# TC4nano_v2.net
KiCad netlist of a schematic drawn in EAGLE
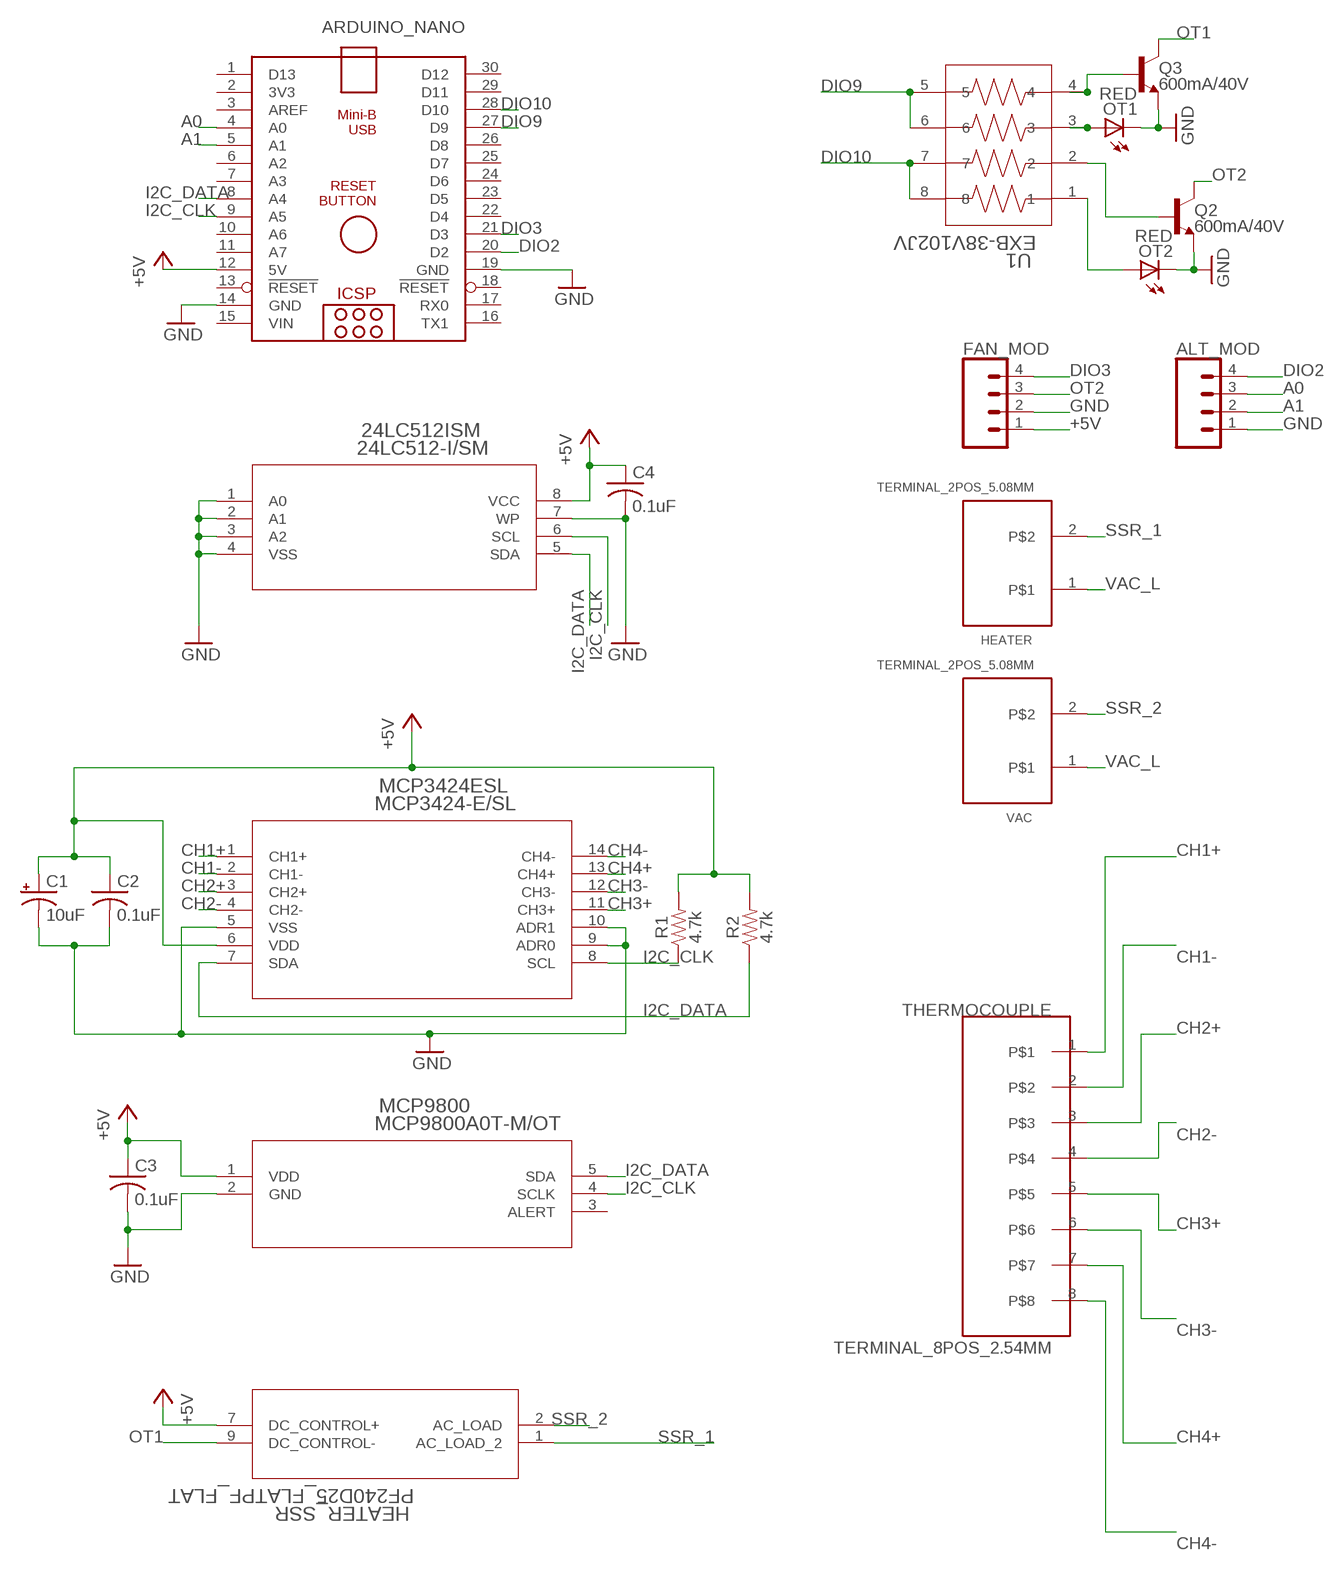
[diagram p0: schematic, sheet 1]

(export (version "E")
  (design (tool "Eeschema 10.0.6"))
  (components
    (comp (ref "24LC512ISM")
      (value "24LC512-I/SM")
      (footprint "eagle-import:SOIC8-W_MC")
      (fields (field (name "MANUFACTURER_PART_NUMBER") "24LC512ISM"))
      (libsource (lib "eagle-import") (part "24LC512-I/SM"))
    )
    (comp (ref "ALT_MOD")
      (value "CONN_04LONGPADS")
      (footprint "eagle-import:1X04_LONGPADS")
      (libsource (lib "eagle-import") (part "CONN_04LONGPADS"))
    )
    (comp (ref "ARDUINO_NANO")
      (value "ARDUINO_NANO")
      (footprint "eagle-import:ARDUINO_NANO")
      (libsource (lib "eagle-import") (part "ARDUINO_NANO"))
    )
    (comp (ref "C1")
      (value "10uF")
      (footprint "eagle-import:EIA3216")
      (libsource (lib "eagle-import") (part "10UF-POLAR-EIA3216-16V-10%(TANT)"))
    )
    (comp (ref "C2")
      (value "0.1uF")
      (footprint "eagle-import:C0805")
      (libsource (lib "eagle-import") (part "C-USC0805"))
    )
    (comp (ref "C3")
      (value "0.1uF")
      (footprint "eagle-import:C0805")
      (libsource (lib "eagle-import") (part "C-USC0805"))
    )
    (comp (ref "C4")
      (value "0.1uF")
      (footprint "eagle-import:C0805")
      (libsource (lib "eagle-import") (part "C-USC0805"))
    )
    (comp (ref "FAN_MOD")
      (value "CONN_04LONGPADS")
      (footprint "eagle-import:1X04_LONGPADS")
      (libsource (lib "eagle-import") (part "CONN_04LONGPADS"))
    )
    (comp (ref "HEATER")
      (value "TERMINAL_2POS_5.08MM")
      (footprint "eagle-import:TERMINAL_2POS_5.08MM")
      (libsource (lib "eagle-import") (part "TERMINAL_2POS_5.08MM"))
    )
    (comp (ref "HEATER_SSR")
      (value "PF240D25_FLATPF_FLAT")
      (footprint "eagle-import:RELAY_PF_FLAT")
      (libsource (lib "eagle-import") (part "PF240D25_FLATPF_FLAT"))
    )
    (comp (ref "MCP3424ESL")
      (value "MCP3424-E/SL")
      (footprint "eagle-import:SOIC14-N_MC")
      (fields (field (name "MANUFACTURER_PART_NUMBER") "MCP3424ESL"))
      (libsource (lib "eagle-import") (part "MCP3424-E/SL"))
    )
    (comp (ref "MCP9800")
      (value "MCP9800A0T-M/OT")
      (footprint "eagle-import:SOT-23-5_MC")
      (fields (field (name "MANUFACTURER_PART_NUMBER") "MCP9800A0TMOT"))
      (libsource (lib "eagle-import") (part "MCP9800A0T-M/OT"))
    )
    (comp (ref "OT1")
      (value "RED")
      (footprint "eagle-import:CHIPLED_0805")
      (libsource (lib "eagle-import") (part "LEDCHIPLED_0805"))
    )
    (comp (ref "OT2")
      (value "RED")
      (footprint "eagle-import:CHIPLED_0805")
      (libsource (lib "eagle-import") (part "LEDCHIPLED_0805"))
    )
    (comp (ref "Q2")
      (value "600mA/40V")
      (footprint "eagle-import:SOT23-3")
      (libsource (lib "eagle-import") (part "TRANS_NPN-MMBT2222AL"))
    )
    (comp (ref "Q3")
      (value "600mA/40V")
      (footprint "eagle-import:SOT23-3")
      (libsource (lib "eagle-import") (part "TRANS_NPN-MMBT2222AL"))
    )
    (comp (ref "R1")
      (value "4.7k")
      (footprint "eagle-import:0603")
      (libsource (lib "eagle-import") (part "4.7KOHM-0603-1/10W-1%"))
    )
    (comp (ref "R2")
      (value "4.7k")
      (footprint "eagle-import:0603")
      (libsource (lib "eagle-import") (part "4.7KOHM-0603-1/10W-1%"))
    )
    (comp (ref "THERMOCOUPLE")
      (value "TERMINAL_8POS_2.54MM")
      (footprint "eagle-import:TERMINAL_8POS_2.54MM")
      (libsource (lib "eagle-import") (part "TERMINAL_8POS_2.54MM"))
    )
    (comp (ref "U1")
      (value "EXB-38V102JV")
      (footprint "eagle-import:C_ARRAY_EXB38V")
      (fields (field (name "MANUFACTURER_PART_NUMBER") "EXB38V102JV"))
      (libsource (lib "eagle-import") (part "EXB-38V102JV"))
    )
    (comp (ref "VAC")
      (value "TERMINAL_2POS_5.08MM")
      (footprint "eagle-import:TERMINAL_2POS_5.08MM")
      (libsource (lib "eagle-import") (part "TERMINAL_2POS_5.08MM"))
    )
  )
  (nets
    (net (code "1") (name "+5V") (class "Default")
      (node (ref "24LC512ISM") (pin "8") (pinfunction "VCC_8") (pintype "passive"))
      (node (ref "ARDUINO_NANO") (pin "12") (pinfunction "5V_12") (pintype "power_in"))
      (node (ref "C1") (pin "+") (pinfunction "+_+") (pintype "passive"))
      (node (ref "C2") (pin "1") (pinfunction "1_1") (pintype "passive"))
      (node (ref "C3") (pin "1") (pinfunction "1_1") (pintype "passive"))
      (node (ref "C4") (pin "1") (pinfunction "1_1") (pintype "passive"))
      (node (ref "FAN_MOD") (pin "1") (pinfunction "1_1") (pintype "passive"))
      (node (ref "HEATER_SSR") (pin "7") (pinfunction "DC_CONTROL+_7") (pintype "passive"))
      (node (ref "MCP3424ESL") (pin "6") (pinfunction "VDD_6") (pintype "power_in"))
      (node (ref "MCP9800") (pin "1") (pinfunction "VDD_1") (pintype "passive"))
      (node (ref "R1") (pin "2") (pinfunction "2_2") (pintype "passive"))
      (node (ref "R2") (pin "2") (pinfunction "2_2") (pintype "passive"))
    )
    (net (code "2") (name "/A0") (class "Default")
      (node (ref "ALT_MOD") (pin "3") (pinfunction "3_3") (pintype "passive"))
      (node (ref "ARDUINO_NANO") (pin "4") (pinfunction "A0_4") (pintype "bidirectional"))
    )
    (net (code "3") (name "/A1") (class "Default")
      (node (ref "ALT_MOD") (pin "2") (pinfunction "2_2") (pintype "passive"))
      (node (ref "ARDUINO_NANO") (pin "5") (pinfunction "A1_5") (pintype "bidirectional"))
    )
    (net (code "4") (name "/CH1+") (class "Default")
      (node (ref "MCP3424ESL") (pin "1") (pinfunction "CH1+_1") (pintype "input"))
      (node (ref "THERMOCOUPLE") (pin "1") (pinfunction "P$1_1") (pintype "bidirectional"))
    )
    (net (code "5") (name "/CH1-") (class "Default")
      (node (ref "MCP3424ESL") (pin "2") (pinfunction "CH1-_2") (pintype "input"))
      (node (ref "THERMOCOUPLE") (pin "2") (pinfunction "P$2_2") (pintype "bidirectional"))
    )
    (net (code "6") (name "/CH2+") (class "Default")
      (node (ref "MCP3424ESL") (pin "3") (pinfunction "CH2+_3") (pintype "input"))
      (node (ref "THERMOCOUPLE") (pin "3") (pinfunction "P$3_3") (pintype "bidirectional"))
    )
    (net (code "7") (name "/CH2-") (class "Default")
      (node (ref "MCP3424ESL") (pin "4") (pinfunction "CH2-_4") (pintype "input"))
      (node (ref "THERMOCOUPLE") (pin "4") (pinfunction "P$4_4") (pintype "bidirectional"))
    )
    (net (code "8") (name "/CH3+") (class "Default")
      (node (ref "MCP3424ESL") (pin "11") (pinfunction "CH3+_11") (pintype "input"))
      (node (ref "THERMOCOUPLE") (pin "5") (pinfunction "P$5_5") (pintype "bidirectional"))
    )
    (net (code "9") (name "/CH3-") (class "Default")
      (node (ref "MCP3424ESL") (pin "12") (pinfunction "CH3-_12") (pintype "input"))
      (node (ref "THERMOCOUPLE") (pin "6") (pinfunction "P$6_6") (pintype "bidirectional"))
    )
    (net (code "10") (name "/CH4+") (class "Default")
      (node (ref "MCP3424ESL") (pin "13") (pinfunction "CH4+_13") (pintype "input"))
      (node (ref "THERMOCOUPLE") (pin "7") (pinfunction "P$7_7") (pintype "bidirectional"))
    )
    (net (code "11") (name "/CH4-") (class "Default")
      (node (ref "MCP3424ESL") (pin "14") (pinfunction "CH4-_14") (pintype "input"))
      (node (ref "THERMOCOUPLE") (pin "8") (pinfunction "P$8_8") (pintype "bidirectional"))
    )
    (net (code "12") (name "/DIO2") (class "Default")
      (node (ref "ALT_MOD") (pin "4") (pinfunction "4_4") (pintype "passive"))
      (node (ref "ARDUINO_NANO") (pin "20") (pinfunction "D2_20") (pintype "bidirectional"))
    )
    (net (code "13") (name "/DIO3") (class "Default")
      (node (ref "ARDUINO_NANO") (pin "21") (pinfunction "D3_21") (pintype "bidirectional"))
      (node (ref "FAN_MOD") (pin "4") (pinfunction "4_4") (pintype "passive"))
    )
    (net (code "14") (name "/DIO9") (class "Default")
      (node (ref "ARDUINO_NANO") (pin "27") (pinfunction "D9_27") (pintype "bidirectional"))
      (node (ref "U1") (pin "5") (pinfunction "5_5") (pintype "passive"))
      (node (ref "U1") (pin "6") (pinfunction "6_6") (pintype "passive"))
    )
    (net (code "15") (name "/DIO10") (class "Default")
      (node (ref "ARDUINO_NANO") (pin "28") (pinfunction "D10_28") (pintype "bidirectional"))
      (node (ref "U1") (pin "7") (pinfunction "7_7") (pintype "passive"))
      (node (ref "U1") (pin "8") (pinfunction "8_8") (pintype "passive"))
    )
    (net (code "16") (name "/I2C_CLK") (class "Default")
      (node (ref "24LC512ISM") (pin "6") (pinfunction "SCL_6") (pintype "input"))
      (node (ref "ARDUINO_NANO") (pin "9") (pinfunction "A5_9") (pintype "bidirectional"))
      (node (ref "MCP3424ESL") (pin "8") (pinfunction "SCL_8") (pintype "input"))
      (node (ref "MCP9800") (pin "4") (pinfunction "SCLK_4") (pintype "passive"))
      (node (ref "R1") (pin "1") (pinfunction "1_1") (pintype "passive"))
    )
    (net (code "17") (name "/I2C_DATA") (class "Default")
      (node (ref "24LC512ISM") (pin "5") (pinfunction "SDA_5") (pintype "bidirectional"))
      (node (ref "ARDUINO_NANO") (pin "8") (pinfunction "A4_8") (pintype "bidirectional"))
      (node (ref "MCP3424ESL") (pin "7") (pinfunction "SDA_7") (pintype "bidirectional"))
      (node (ref "MCP9800") (pin "5") (pinfunction "SDA_5") (pintype "passive"))
      (node (ref "R2") (pin "1") (pinfunction "1_1") (pintype "passive"))
    )
    (net (code "18") (name "/OT1") (class "Default")
      (node (ref "HEATER_SSR") (pin "9") (pinfunction "DC_CONTROL-_9") (pintype "passive"))
      (node (ref "Q3") (pin "3") (pinfunction "C_3") (pintype "passive"))
    )
    (net (code "19") (name "/OT2") (class "Default")
      (node (ref "FAN_MOD") (pin "3") (pinfunction "3_3") (pintype "passive"))
      (node (ref "Q2") (pin "3") (pinfunction "C_3") (pintype "passive"))
    )
    (net (code "20") (name "/SSR_1") (class "Default")
      (node (ref "HEATER") (pin "2") (pinfunction "P$2_2") (pintype "bidirectional"))
      (node (ref "HEATER_SSR") (pin "1") (pinfunction "AC_LOAD_2_1") (pintype "passive"))
    )
    (net (code "21") (name "/SSR_2") (class "Default")
      (node (ref "HEATER_SSR") (pin "2") (pinfunction "AC_LOAD_2") (pintype "passive"))
      (node (ref "VAC") (pin "2") (pinfunction "P$2_2") (pintype "bidirectional"))
    )
    (net (code "22") (name "/VAC_L") (class "Default")
      (node (ref "HEATER") (pin "1") (pinfunction "P$1_1") (pintype "bidirectional"))
      (node (ref "VAC") (pin "1") (pinfunction "P$1_1") (pintype "bidirectional"))
    )
    (net (code "23") (name "/VIN") (class "Default")
      (node (ref "ARDUINO_NANO") (pin "15") (pinfunction "VIN_15") (pintype "power_in"))
    )
    (net (code "24") (name "GND") (class "Default")
      (node (ref "24LC512ISM") (pin "1") (pinfunction "A0_1") (pintype "input"))
      (node (ref "24LC512ISM") (pin "2") (pinfunction "A1_2") (pintype "input"))
      (node (ref "24LC512ISM") (pin "3") (pinfunction "A2_3") (pintype "input"))
      (node (ref "24LC512ISM") (pin "4") (pinfunction "VSS_4") (pintype "passive"))
      (node (ref "24LC512ISM") (pin "7") (pinfunction "WP_7") (pintype "input"))
      (node (ref "ALT_MOD") (pin "1") (pinfunction "1_1") (pintype "passive"))
      (node (ref "ARDUINO_NANO") (pin "14") (pinfunction "GND_14") (pintype "power_in"))
      (node (ref "ARDUINO_NANO") (pin "19") (pinfunction "GND_19") (pintype "power_in"))
      (node (ref "C1") (pin "-") (pinfunction "-_-") (pintype "passive"))
      (node (ref "C2") (pin "2") (pinfunction "2_2") (pintype "passive"))
      (node (ref "C3") (pin "2") (pinfunction "2_2") (pintype "passive"))
      (node (ref "C4") (pin "2") (pinfunction "2_2") (pintype "passive"))
      (node (ref "FAN_MOD") (pin "2") (pinfunction "2_2") (pintype "passive"))
      (node (ref "MCP3424ESL") (pin "10") (pinfunction "ADR1_10") (pintype "passive"))
      (node (ref "MCP3424ESL") (pin "5") (pinfunction "VSS_5") (pintype "power_in"))
      (node (ref "MCP3424ESL") (pin "9") (pinfunction "ADR0_9") (pintype "passive"))
      (node (ref "MCP9800") (pin "2") (pinfunction "GND_2") (pintype "passive"))
      (node (ref "OT1") (pin "C") (pinfunction "C_C") (pintype "passive"))
      (node (ref "OT2") (pin "C") (pinfunction "C_C") (pintype "passive"))
      (node (ref "Q2") (pin "2") (pinfunction "E_2") (pintype "passive"))
      (node (ref "Q3") (pin "2") (pinfunction "E_2") (pintype "passive"))
    )
    (net (code "25") (name "Net-(OT1-PadA)") (class "Default")
      (node (ref "OT1") (pin "A") (pinfunction "A_A") (pintype "passive"))
      (node (ref "U1") (pin "3") (pinfunction "3_3") (pintype "passive"))
    )
    (net (code "26") (name "Net-(OT2-PadA)") (class "Default")
      (node (ref "OT2") (pin "A") (pinfunction "A_A") (pintype "passive"))
      (node (ref "U1") (pin "1") (pinfunction "1_1") (pintype "passive"))
    )
    (net (code "27") (name "Net-(Q2-B)") (class "Default")
      (node (ref "Q2") (pin "1") (pinfunction "B_1") (pintype "passive"))
      (node (ref "U1") (pin "2") (pinfunction "2_2") (pintype "passive"))
    )
    (net (code "28") (name "Net-(Q3-B)") (class "Default")
      (node (ref "Q3") (pin "1") (pinfunction "B_1") (pintype "passive"))
      (node (ref "U1") (pin "4") (pinfunction "4_4") (pintype "passive"))
    )
    (net (code "29") (name "unconnected-(ARDUINO_NANO-3V3-Pad2)") (class "Default")
      (node (ref "ARDUINO_NANO") (pin "2") (pinfunction "3V3_2") (pintype "output"))
    )
    (net (code "30") (name "unconnected-(ARDUINO_NANO-A2-Pad6)") (class "Default")
      (node (ref "ARDUINO_NANO") (pin "6") (pinfunction "A2_6") (pintype "bidirectional"))
    )
    (net (code "31") (name "unconnected-(ARDUINO_NANO-A3-Pad7)") (class "Default")
      (node (ref "ARDUINO_NANO") (pin "7") (pinfunction "A3_7") (pintype "bidirectional"))
    )
    (net (code "32") (name "unconnected-(ARDUINO_NANO-A6-Pad10)") (class "Default")
      (node (ref "ARDUINO_NANO") (pin "10") (pinfunction "A6_10") (pintype "bidirectional"))
    )
    (net (code "33") (name "unconnected-(ARDUINO_NANO-A7-Pad11)") (class "Default")
      (node (ref "ARDUINO_NANO") (pin "11") (pinfunction "A7_11") (pintype "bidirectional"))
    )
    (net (code "34") (name "unconnected-(ARDUINO_NANO-AREF-Pad3)") (class "Default")
      (node (ref "ARDUINO_NANO") (pin "3") (pinfunction "AREF_3") (pintype "input"))
    )
    (net (code "35") (name "unconnected-(ARDUINO_NANO-D4-Pad22)") (class "Default")
      (node (ref "ARDUINO_NANO") (pin "22") (pinfunction "D4_22") (pintype "bidirectional"))
    )
    (net (code "36") (name "unconnected-(ARDUINO_NANO-D5-Pad23)") (class "Default")
      (node (ref "ARDUINO_NANO") (pin "23") (pinfunction "D5_23") (pintype "bidirectional"))
    )
    (net (code "37") (name "unconnected-(ARDUINO_NANO-D6-Pad24)") (class "Default")
      (node (ref "ARDUINO_NANO") (pin "24") (pinfunction "D6_24") (pintype "bidirectional"))
    )
    (net (code "38") (name "unconnected-(ARDUINO_NANO-D7-Pad25)") (class "Default")
      (node (ref "ARDUINO_NANO") (pin "25") (pinfunction "D7_25") (pintype "bidirectional"))
    )
    (net (code "39") (name "unconnected-(ARDUINO_NANO-D8-Pad26)") (class "Default")
      (node (ref "ARDUINO_NANO") (pin "26") (pinfunction "D8_26") (pintype "bidirectional"))
    )
    (net (code "40") (name "unconnected-(ARDUINO_NANO-D11-Pad29)") (class "Default")
      (node (ref "ARDUINO_NANO") (pin "29") (pinfunction "D11_29") (pintype "bidirectional"))
    )
    (net (code "41") (name "unconnected-(ARDUINO_NANO-D12-Pad30)") (class "Default")
      (node (ref "ARDUINO_NANO") (pin "30") (pinfunction "D12_30") (pintype "bidirectional"))
    )
    (net (code "42") (name "unconnected-(ARDUINO_NANO-D13-Pad1)") (class "Default")
      (node (ref "ARDUINO_NANO") (pin "1") (pinfunction "D13_1") (pintype "bidirectional"))
    )
    (net (code "43") (name "unconnected-(ARDUINO_NANO-RX0-Pad17)") (class "Default")
      (node (ref "ARDUINO_NANO") (pin "17") (pinfunction "RX0_17") (pintype "bidirectional"))
    )
    (net (code "44") (name "unconnected-(ARDUINO_NANO-TX1-Pad16)") (class "Default")
      (node (ref "ARDUINO_NANO") (pin "16") (pinfunction "TX1_16") (pintype "bidirectional"))
    )
    (net (code "45") (name "unconnected-(ARDUINO_NANO-~{RESET}-Pad13)") (class "Default")
      (node (ref "ARDUINO_NANO") (pin "13") (pinfunction "~{RESET}_13") (pintype "input"))
    )
    (net (code "46") (name "unconnected-(ARDUINO_NANO-~{RESET}-Pad18)") (class "Default")
      (node (ref "ARDUINO_NANO") (pin "18") (pinfunction "~{RESET}_18") (pintype "input"))
    )
    (net (code "47") (name "unconnected-(MCP9800-ALERT-Pad3)") (class "Default")
      (node (ref "MCP9800") (pin "3") (pinfunction "ALERT_3") (pintype "passive"))
    )
  )
)
